# InterfaceExtension.net
KiCad netlist of a schematic drawn in Altium Designer
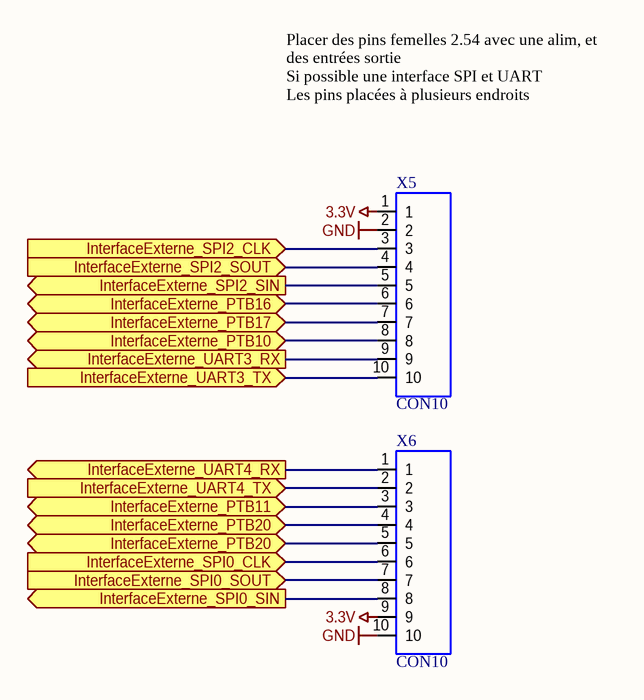
[diagram p0: InterfaceExtension.SchDoc]

(export (version "E")
  (design (tool "Eeschema 10.0.6"))
  (components
    (comp (ref "X5") (value "CON10") (footprint "SIP10") (libsource (lib "EISI") (part "CON10")))
    (comp (ref "X6") (value "CON10") (footprint "SIP10") (libsource (lib "EISI") (part "CON10")))
  )
  (nets
    (net (code "1") (name "/InterfaceExterne_PTB10") (class "Default")
      (node (ref "X5") (pin "8") (pinfunction "8_8") (pintype "passive"))
    )
    (net (code "2") (name "/InterfaceExterne_PTB11") (class "Default")
      (node (ref "X6") (pin "3") (pinfunction "3_3") (pintype "passive"))
    )
    (net (code "3") (name "/InterfaceExterne_PTB16") (class "Default")
      (node (ref "X5") (pin "6") (pinfunction "6_6") (pintype "passive"))
    )
    (net (code "4") (name "/InterfaceExterne_PTB17") (class "Default")
      (node (ref "X5") (pin "7") (pinfunction "7_7") (pintype "passive"))
    )
    (net (code "5") (name "/InterfaceExterne_PTB20") (class "Default")
      (node (ref "X6") (pin "4") (pinfunction "4_4") (pintype "passive"))
      (node (ref "X6") (pin "5") (pinfunction "5_5") (pintype "passive"))
    )
    (net (code "6") (name "/InterfaceExterne_SPI0_CLK") (class "Default")
      (node (ref "X6") (pin "6") (pinfunction "6_6") (pintype "passive"))
    )
    (net (code "7") (name "/InterfaceExterne_SPI0_SIN") (class "Default")
      (node (ref "X6") (pin "8") (pinfunction "8_8") (pintype "passive"))
    )
    (net (code "8") (name "/InterfaceExterne_SPI0_SOUT") (class "Default")
      (node (ref "X6") (pin "7") (pinfunction "7_7") (pintype "passive"))
    )
    (net (code "9") (name "/InterfaceExterne_SPI2_CLK") (class "Default")
      (node (ref "X5") (pin "3") (pinfunction "3_3") (pintype "passive"))
    )
    (net (code "10") (name "/InterfaceExterne_SPI2_SIN") (class "Default")
      (node (ref "X5") (pin "5") (pinfunction "5_5") (pintype "passive"))
    )
    (net (code "11") (name "/InterfaceExterne_SPI2_SOUT") (class "Default")
      (node (ref "X5") (pin "4") (pinfunction "4_4") (pintype "passive"))
    )
    (net (code "12") (name "/InterfaceExterne_UART3_RX") (class "Default")
      (node (ref "X5") (pin "9") (pinfunction "9_9") (pintype "passive"))
    )
    (net (code "13") (name "/InterfaceExterne_UART3_TX") (class "Default")
      (node (ref "X5") (pin "10") (pinfunction "10_10") (pintype "passive"))
    )
    (net (code "14") (name "/InterfaceExterne_UART4_RX") (class "Default")
      (node (ref "X6") (pin "1") (pinfunction "1_1") (pintype "passive"))
    )
    (net (code "15") (name "/InterfaceExterne_UART4_TX") (class "Default")
      (node (ref "X6") (pin "2") (pinfunction "2_2") (pintype "passive"))
    )
    (net (code "16") (name "3.3V") (class "Default")
      (node (ref "X5") (pin "1") (pinfunction "1_1") (pintype "passive"))
      (node (ref "X6") (pin "9") (pinfunction "9_9") (pintype "passive"))
    )
    (net (code "17") (name "GND") (class "Default")
      (node (ref "X5") (pin "2") (pinfunction "2_2") (pintype "passive"))
      (node (ref "X6") (pin "10") (pinfunction "10_10") (pintype "passive"))
    )
  )
)
